# Garoa_Dojo_Shield.net
KiCad netlist of a schematic drawn in EAGLE
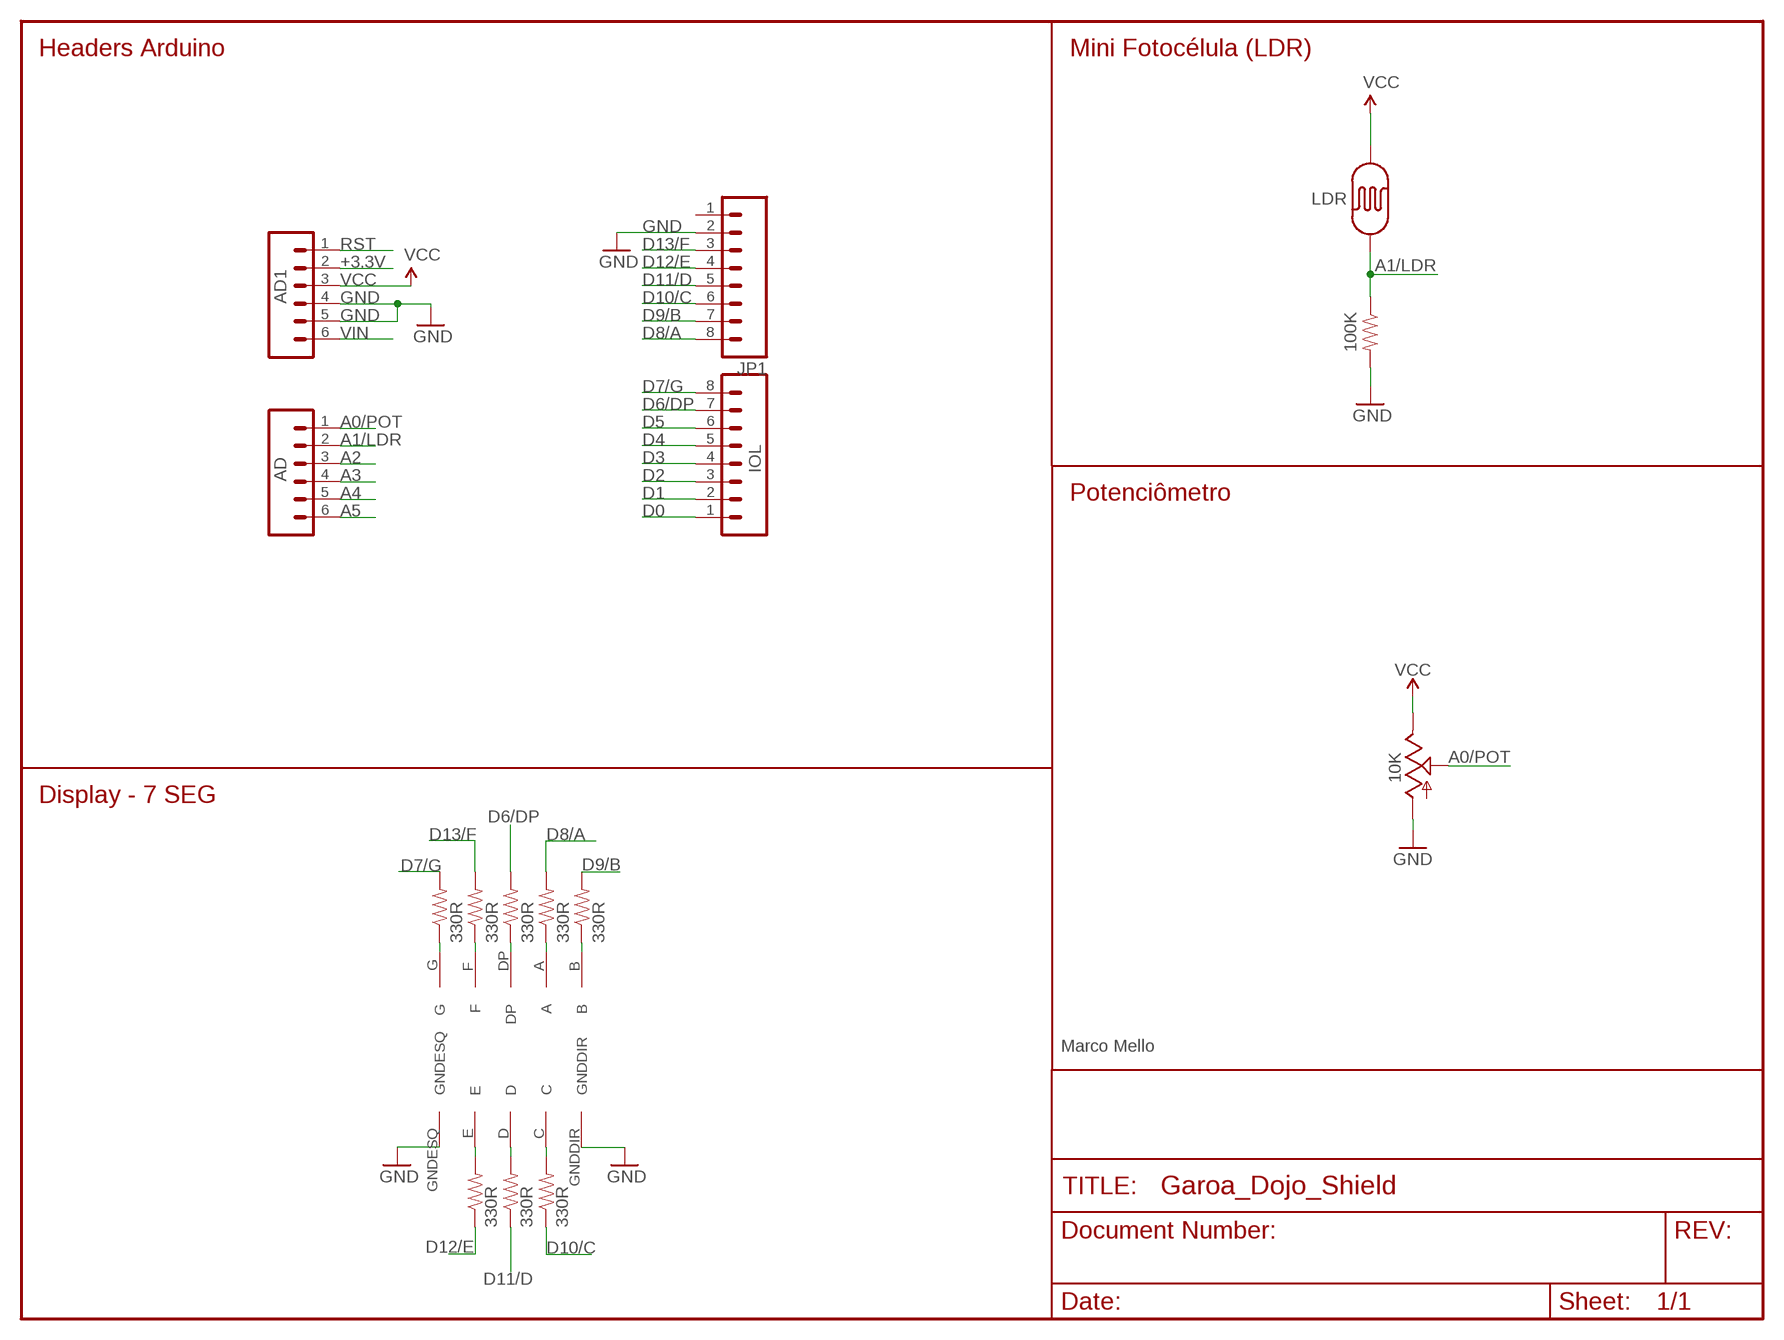
[diagram p0: schematic, sheet 1]

(export (version "E")
  (design (tool "Eeschema 10.0.6"))
  (components
    (comp (ref "AD")
      (value "M06SIP")
      (footprint "eagle-import:1X06")
      (libsource (lib "eagle-import") (part "M06SIP"))
    )
    (comp (ref "AD1")
      (value "M06SIP")
      (footprint "eagle-import:1X06")
      (libsource (lib "eagle-import") (part "M06SIP"))
    )
    (comp (ref "IOL")
      (value "M08")
      (footprint "eagle-import:1X08")
      (libsource (lib "eagle-import") (part "M08"))
    )
    (comp (ref "JP1")
      (value "M081X08")
      (footprint "eagle-import:1X08")
      (libsource (lib "eagle-import") (part "M081X08"))
    )
    (comp (ref "R1")
      (value "LDR")
      (footprint "eagle-import:PHOTOCELL")
      (libsource (lib "eagle-import") (part "PHOTOCELLPTH"))
    )
    (comp (ref "R2")
      (value "330R")
      (footprint "eagle-import:AXIAL-0.3-KIT")
      (libsource (lib "eagle-import") (part "RESISTORKIT"))
    )
    (comp (ref "R3")
      (value "330R")
      (footprint "eagle-import:AXIAL-0.3-KIT")
      (libsource (lib "eagle-import") (part "RESISTORKIT"))
    )
    (comp (ref "R4")
      (value "330R")
      (footprint "eagle-import:AXIAL-0.3-KIT")
      (libsource (lib "eagle-import") (part "RESISTORKIT"))
    )
    (comp (ref "R5")
      (value "330R")
      (footprint "eagle-import:AXIAL-0.3-KIT")
      (libsource (lib "eagle-import") (part "RESISTORKIT"))
    )
    (comp (ref "R6")
      (value "330R")
      (footprint "eagle-import:AXIAL-0.3-KIT")
      (libsource (lib "eagle-import") (part "RESISTORKIT"))
    )
    (comp (ref "R7")
      (value "330R")
      (footprint "eagle-import:AXIAL-0.3-KIT")
      (libsource (lib "eagle-import") (part "RESISTORKIT"))
    )
    (comp (ref "R8")
      (value "330R")
      (footprint "eagle-import:AXIAL-0.3-KIT")
      (libsource (lib "eagle-import") (part "RESISTORKIT"))
    )
    (comp (ref "R9")
      (value "330R")
      (footprint "eagle-import:AXIAL-0.3-KIT")
      (libsource (lib "eagle-import") (part "RESISTORKIT"))
    )
    (comp (ref "R10")
      (value "100K")
      (footprint "eagle-import:AXIAL-0.3-KIT")
      (libsource (lib "eagle-import") (part "RESISTORKIT"))
    )
    (comp (ref "U$1")
      (value "10K")
      (footprint "eagle-import:POT_ALPHA_RV16AF-20")
      (libsource (lib "eagle-import") (part "POT-RV16AF-20"))
    )
    (comp (ref "U$2")
      (value "7SEG-CODINGDOJO")
      (footprint "eagle-import:7SEG-CODINGDOJO")
      (libsource (lib "eagle-import") (part "7SEG-CODINGDOJO"))
    )
  )
  (nets
    (net (code "1") (name "/+3.3V") (class "Default")
      (node (ref "AD1") (pin "2") (pinfunction "2_2") (pintype "passive"))
    )
    (net (code "2") (name "/A0{slash}POT") (class "Default")
      (node (ref "AD") (pin "1") (pinfunction "1_1") (pintype "passive"))
      (node (ref "U$1") (pin "2") (pinfunction "S_2") (pintype "passive"))
    )
    (net (code "3") (name "/A1{slash}LDR") (class "Default")
      (node (ref "AD") (pin "2") (pinfunction "2_2") (pintype "passive"))
      (node (ref "R1") (pin "1") (pinfunction "P$1_1") (pintype "bidirectional"))
      (node (ref "R10") (pin "P$1") (pinfunction "1_P$1") (pintype "passive"))
    )
    (net (code "4") (name "/A2") (class "Default")
      (node (ref "AD") (pin "3") (pinfunction "3_3") (pintype "passive"))
    )
    (net (code "5") (name "/A3") (class "Default")
      (node (ref "AD") (pin "4") (pinfunction "4_4") (pintype "passive"))
    )
    (net (code "6") (name "/A4") (class "Default")
      (node (ref "AD") (pin "5") (pinfunction "5_5") (pintype "passive"))
    )
    (net (code "7") (name "/A5") (class "Default")
      (node (ref "AD") (pin "6") (pinfunction "6_6") (pintype "passive"))
    )
    (net (code "8") (name "/D0") (class "Default")
      (node (ref "IOL") (pin "1") (pinfunction "1_1") (pintype "passive"))
    )
    (net (code "9") (name "/D1") (class "Default")
      (node (ref "IOL") (pin "2") (pinfunction "2_2") (pintype "passive"))
    )
    (net (code "10") (name "/D2") (class "Default")
      (node (ref "IOL") (pin "3") (pinfunction "3_3") (pintype "passive"))
    )
    (net (code "11") (name "/D3") (class "Default")
      (node (ref "IOL") (pin "4") (pinfunction "4_4") (pintype "passive"))
    )
    (net (code "12") (name "/D4") (class "Default")
      (node (ref "IOL") (pin "5") (pinfunction "5_5") (pintype "passive"))
    )
    (net (code "13") (name "/D5") (class "Default")
      (node (ref "IOL") (pin "6") (pinfunction "6_6") (pintype "passive"))
    )
    (net (code "14") (name "/D6{slash}DP") (class "Default")
      (node (ref "IOL") (pin "7") (pinfunction "7_7") (pintype "passive"))
      (node (ref "R4") (pin "P$2") (pinfunction "2_P$2") (pintype "passive"))
    )
    (net (code "15") (name "/D7{slash}G") (class "Default")
      (node (ref "IOL") (pin "8") (pinfunction "8_8") (pintype "passive"))
      (node (ref "R2") (pin "P$2") (pinfunction "2_P$2") (pintype "passive"))
    )
    (net (code "16") (name "/D8{slash}A") (class "Default")
      (node (ref "JP1") (pin "8") (pinfunction "8_8") (pintype "passive"))
      (node (ref "R5") (pin "P$2") (pinfunction "2_P$2") (pintype "passive"))
    )
    (net (code "17") (name "/D9{slash}B") (class "Default")
      (node (ref "JP1") (pin "7") (pinfunction "7_7") (pintype "passive"))
      (node (ref "R6") (pin "P$2") (pinfunction "2_P$2") (pintype "passive"))
    )
    (net (code "18") (name "/D10{slash}C") (class "Default")
      (node (ref "JP1") (pin "6") (pinfunction "6_6") (pintype "passive"))
      (node (ref "R7") (pin "P$1") (pinfunction "1_P$1") (pintype "passive"))
    )
    (net (code "19") (name "/D11{slash}D") (class "Default")
      (node (ref "JP1") (pin "5") (pinfunction "5_5") (pintype "passive"))
      (node (ref "R8") (pin "P$1") (pinfunction "1_P$1") (pintype "passive"))
    )
    (net (code "20") (name "/D12{slash}E") (class "Default")
      (node (ref "JP1") (pin "4") (pinfunction "4_4") (pintype "passive"))
      (node (ref "R9") (pin "P$1") (pinfunction "1_P$1") (pintype "passive"))
    )
    (net (code "21") (name "/D13{slash}F") (class "Default")
      (node (ref "JP1") (pin "3") (pinfunction "3_3") (pintype "passive"))
      (node (ref "R3") (pin "P$2") (pinfunction "2_P$2") (pintype "passive"))
    )
    (net (code "22") (name "/RST") (class "Default")
      (node (ref "AD1") (pin "1") (pinfunction "1_1") (pintype "passive"))
    )
    (net (code "23") (name "/VIN") (class "Default")
      (node (ref "AD1") (pin "6") (pinfunction "6_6") (pintype "passive"))
    )
    (net (code "24") (name "GND") (class "Default")
      (node (ref "AD1") (pin "4") (pinfunction "4_4") (pintype "passive"))
      (node (ref "AD1") (pin "5") (pinfunction "5_5") (pintype "passive"))
      (node (ref "JP1") (pin "2") (pinfunction "2_2") (pintype "passive"))
      (node (ref "R10") (pin "P$2") (pinfunction "2_P$2") (pintype "passive"))
      (node (ref "U$1") (pin "1") (pinfunction "A_1") (pintype "passive"))
      (node (ref "U$2") (pin "GNDDIR") (pinfunction "GNDDIR_GNDDIR") (pintype "bidirectional"))
      (node (ref "U$2") (pin "GNDESQ") (pinfunction "GNDESQ_GNDESQ") (pintype "bidirectional"))
    )
    (net (code "25") (name "Net-(R2-1)") (class "Default")
      (node (ref "R2") (pin "P$1") (pinfunction "1_P$1") (pintype "passive"))
      (node (ref "U$2") (pin "G") (pinfunction "G_G") (pintype "bidirectional"))
    )
    (net (code "26") (name "Net-(R3-1)") (class "Default")
      (node (ref "R3") (pin "P$1") (pinfunction "1_P$1") (pintype "passive"))
      (node (ref "U$2") (pin "F") (pinfunction "F_F") (pintype "bidirectional"))
    )
    (net (code "27") (name "Net-(R4-1)") (class "Default")
      (node (ref "R4") (pin "P$1") (pinfunction "1_P$1") (pintype "passive"))
      (node (ref "U$2") (pin "DP") (pinfunction "DP_DP") (pintype "bidirectional"))
    )
    (net (code "28") (name "Net-(R5-1)") (class "Default")
      (node (ref "R5") (pin "P$1") (pinfunction "1_P$1") (pintype "passive"))
      (node (ref "U$2") (pin "A") (pinfunction "A_A") (pintype "bidirectional"))
    )
    (net (code "29") (name "Net-(R6-1)") (class "Default")
      (node (ref "R6") (pin "P$1") (pinfunction "1_P$1") (pintype "passive"))
      (node (ref "U$2") (pin "B") (pinfunction "B_B") (pintype "bidirectional"))
    )
    (net (code "30") (name "Net-(R7-2)") (class "Default")
      (node (ref "R7") (pin "P$2") (pinfunction "2_P$2") (pintype "passive"))
      (node (ref "U$2") (pin "C") (pinfunction "C_C") (pintype "bidirectional"))
    )
    (net (code "31") (name "Net-(R8-2)") (class "Default")
      (node (ref "R8") (pin "P$2") (pinfunction "2_P$2") (pintype "passive"))
      (node (ref "U$2") (pin "D") (pinfunction "D_D") (pintype "bidirectional"))
    )
    (net (code "32") (name "Net-(R9-2)") (class "Default")
      (node (ref "R9") (pin "P$2") (pinfunction "2_P$2") (pintype "passive"))
      (node (ref "U$2") (pin "E") (pinfunction "E_E") (pintype "bidirectional"))
    )
    (net (code "33") (name "VCC") (class "Default")
      (node (ref "AD1") (pin "3") (pinfunction "3_3") (pintype "passive"))
      (node (ref "R1") (pin "2") (pinfunction "P$2_2") (pintype "bidirectional"))
      (node (ref "U$1") (pin "3") (pinfunction "E_3") (pintype "passive"))
    )
    (net (code "34") (name "unconnected-(JP1-Pad1)") (class "Default")
      (node (ref "JP1") (pin "1") (pinfunction "1_1") (pintype "passive"))
    )
  )
)
